# low_side_mcu.net
KiCad netlist of a schematic drawn in EAGLE
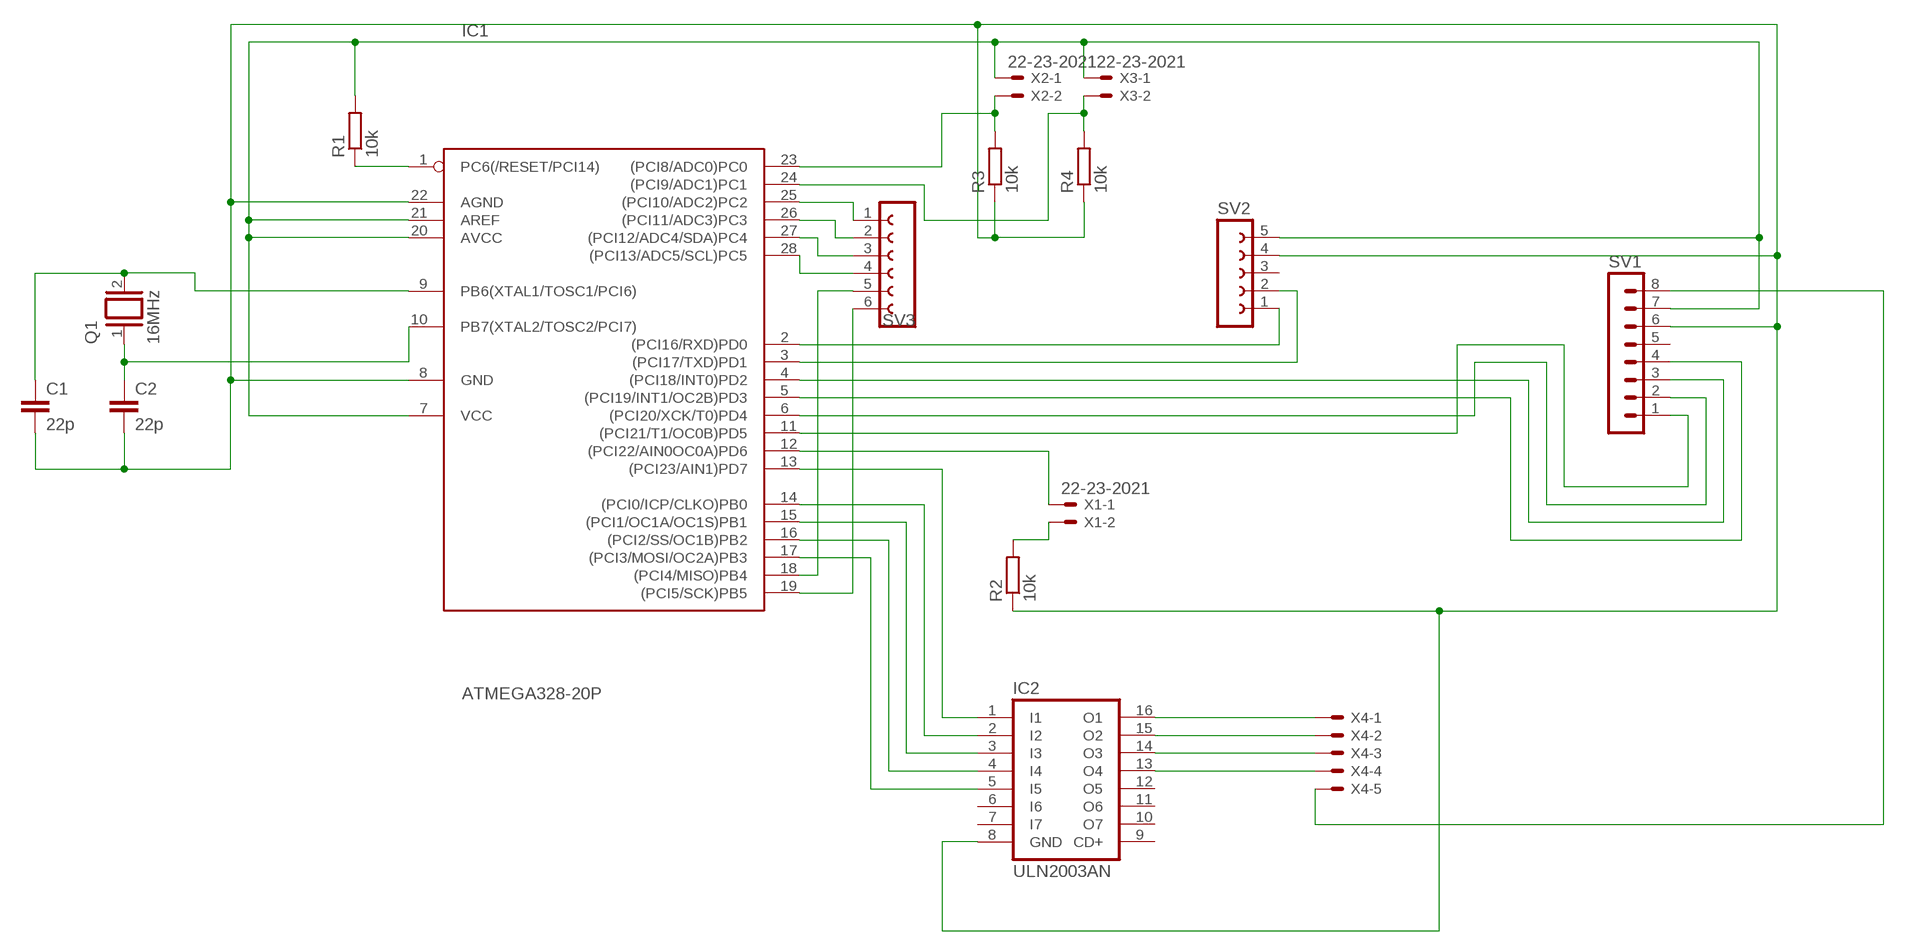
[diagram p0: schematic, sheet 1]

(export (version "E")
  (design (tool "Eeschema 10.0.6"))
  (components
    (comp (ref "C1")
      (value "22p")
      (footprint "eagle-import:C025-024X044")
      (libsource (lib "eagle-import") (part "C-EU025-024X044"))
    )
    (comp (ref "C2")
      (value "22p")
      (footprint "eagle-import:C025-024X044")
      (libsource (lib "eagle-import") (part "C-EU025-024X044"))
    )
    (comp (ref "IC1")
      (value "ATMEGA328-20P")
      (footprint "eagle-import:DIL28-3")
      (libsource (lib "eagle-import") (part "ATMEGA328P-20"))
    )
    (comp (ref "IC2")
      (value "ULN2003AN")
      (footprint "eagle-import:DIL16")
      (libsource (lib "eagle-import") (part "ULN2003AN"))
    )
    (comp (ref "Q1")
      (value "16MHz")
      (footprint "eagle-import:Q")
      (libsource (lib "eagle-import") (part "XTAL"))
    )
    (comp (ref "R1")
      (value "10k")
      (footprint "eagle-import:0204_5")
      (libsource (lib "eagle-import") (part "R-EU_0204/5"))
    )
    (comp (ref "R2")
      (value "10k")
      (footprint "eagle-import:0204_5")
      (libsource (lib "eagle-import") (part "R-EU_0204/5"))
    )
    (comp (ref "R3")
      (value "10k")
      (footprint "eagle-import:0204_5")
      (libsource (lib "eagle-import") (part "R-EU_0204/5"))
    )
    (comp (ref "R4")
      (value "10k")
      (footprint "eagle-import:0204_5")
      (libsource (lib "eagle-import") (part "R-EU_0204/5"))
    )
    (comp (ref "SV1")
      (value "MA08-1")
      (footprint "eagle-import:MA08-1")
      (libsource (lib "eagle-import") (part "MA08-1"))
    )
    (comp (ref "SV2")
      (value "FE05-1")
      (footprint "eagle-import:FE05-1")
      (libsource (lib "eagle-import") (part "FE05-1"))
    )
    (comp (ref "SV3")
      (value "FE06-1")
      (footprint "eagle-import:FE06")
      (libsource (lib "eagle-import") (part "FE06-1"))
    )
    (comp (ref "X1")
      (value "22-23-2021")
      (footprint "eagle-import:22-23-2021")
      (fields (field (name "MF") "MOLEX"))
      (libsource (lib "eagle-import") (part "22-23-2021"))
    )
    (comp (ref "X2")
      (value "22-23-2021")
      (footprint "eagle-import:22-23-2021")
      (fields (field (name "MF") "MOLEX"))
      (libsource (lib "eagle-import") (part "22-23-2021"))
    )
    (comp (ref "X3")
      (value "22-23-2021")
      (footprint "eagle-import:22-23-2021")
      (fields (field (name "MF") "MOLEX"))
      (libsource (lib "eagle-import") (part "22-23-2021"))
    )
    (comp (ref "X4")
      (value "KK-156-5")
      (footprint "eagle-import:KK-156-5")
      (fields (field (name "MF") "MOLEX"))
      (libsource (lib "eagle-import") (part "KK-156-5"))
    )
  )
  (nets
    (net (code "1") (name "Net-(IC1-(PCI0{slash}ICP{slash}CLKO)PB0)") (class "Default")
      (node (ref "IC1") (pin "14") (pinfunction "(PCI0/ICP/CLKO)PB0_14") (pintype "bidirectional"))
      (node (ref "IC2") (pin "2") (pinfunction "I2_2") (pintype "input"))
    )
    (net (code "2") (name "Net-(IC1-(PCI1{slash}OC1A{slash}OC1S)PB1)") (class "Default")
      (node (ref "IC1") (pin "15") (pinfunction "(PCI1/OC1A/OC1S)PB1_15") (pintype "bidirectional"))
      (node (ref "IC2") (pin "3") (pinfunction "I3_3") (pintype "input"))
    )
    (net (code "3") (name "Net-(IC1-(PCI2{slash}SS{slash}OC1B)PB2)") (class "Default")
      (node (ref "IC1") (pin "16") (pinfunction "(PCI2/SS/OC1B)PB2_16") (pintype "bidirectional"))
      (node (ref "IC2") (pin "4") (pinfunction "I4_4") (pintype "input"))
    )
    (net (code "4") (name "Net-(IC1-(PCI3{slash}MOSI{slash}OC2A)PB3)") (class "Default")
      (node (ref "IC1") (pin "17") (pinfunction "(PCI3/MOSI/OC2A)PB3_17") (pintype "bidirectional"))
      (node (ref "IC2") (pin "5") (pinfunction "I5_5") (pintype "input"))
    )
    (net (code "5") (name "Net-(IC1-(PCI4{slash}MISO)PB4)") (class "Default")
      (node (ref "IC1") (pin "18") (pinfunction "(PCI4/MISO)PB4_18") (pintype "bidirectional"))
      (node (ref "SV3") (pin "5") (pinfunction "5_5") (pintype "passive"))
    )
    (net (code "6") (name "Net-(IC1-(PCI5{slash}SCK)PB5)") (class "Default")
      (node (ref "IC1") (pin "19") (pinfunction "(PCI5/SCK)PB5_19") (pintype "bidirectional"))
      (node (ref "SV3") (pin "6") (pinfunction "6_6") (pintype "passive"))
    )
    (net (code "7") (name "Net-(IC1-(PCI8{slash}ADC0)PC0)") (class "Default")
      (node (ref "IC1") (pin "23") (pinfunction "(PCI8/ADC0)PC0_23") (pintype "bidirectional"))
      (node (ref "R3") (pin "2") (pinfunction "2_2") (pintype "passive"))
      (node (ref "X2") (pin "2") (pinfunction "S_2") (pintype "passive"))
    )
    (net (code "8") (name "Net-(IC1-(PCI9{slash}ADC1)PC1)") (class "Default")
      (node (ref "IC1") (pin "24") (pinfunction "(PCI9/ADC1)PC1_24") (pintype "bidirectional"))
      (node (ref "R4") (pin "2") (pinfunction "2_2") (pintype "passive"))
      (node (ref "X3") (pin "2") (pinfunction "S_2") (pintype "passive"))
    )
    (net (code "9") (name "Net-(IC1-(PCI10{slash}ADC2)PC2)") (class "Default")
      (node (ref "IC1") (pin "25") (pinfunction "(PCI10/ADC2)PC2_25") (pintype "bidirectional"))
      (node (ref "SV3") (pin "1") (pinfunction "1_1") (pintype "passive"))
    )
    (net (code "10") (name "Net-(IC1-(PCI11{slash}ADC3)PC3)") (class "Default")
      (node (ref "IC1") (pin "26") (pinfunction "(PCI11/ADC3)PC3_26") (pintype "bidirectional"))
      (node (ref "SV3") (pin "2") (pinfunction "2_2") (pintype "passive"))
    )
    (net (code "11") (name "Net-(IC1-(PCI12{slash}ADC4{slash}SDA)PC4)") (class "Default")
      (node (ref "IC1") (pin "27") (pinfunction "(PCI12/ADC4/SDA)PC4_27") (pintype "bidirectional"))
      (node (ref "SV3") (pin "3") (pinfunction "3_3") (pintype "passive"))
    )
    (net (code "12") (name "Net-(IC1-(PCI13{slash}ADC5{slash}SCL)PC5)") (class "Default")
      (node (ref "IC1") (pin "28") (pinfunction "(PCI13/ADC5/SCL)PC5_28") (pintype "bidirectional"))
      (node (ref "SV3") (pin "4") (pinfunction "4_4") (pintype "passive"))
    )
    (net (code "13") (name "Net-(IC1-(PCI16{slash}RXD)PD0)") (class "Default")
      (node (ref "IC1") (pin "2") (pinfunction "(PCI16/RXD)PD0_2") (pintype "bidirectional"))
      (node (ref "SV2") (pin "1") (pinfunction "1_1") (pintype "passive"))
    )
    (net (code "14") (name "Net-(IC1-(PCI17{slash}TXD)PD1)") (class "Default")
      (node (ref "IC1") (pin "3") (pinfunction "(PCI17/TXD)PD1_3") (pintype "bidirectional"))
      (node (ref "SV2") (pin "2") (pinfunction "2_2") (pintype "passive"))
    )
    (net (code "15") (name "Net-(IC1-(PCI18{slash}INT0)PD2)") (class "Default")
      (node (ref "IC1") (pin "4") (pinfunction "(PCI18/INT0)PD2_4") (pintype "bidirectional"))
      (node (ref "SV1") (pin "3") (pinfunction "3_3") (pintype "passive"))
    )
    (net (code "16") (name "Net-(IC1-(PCI19{slash}INT1{slash}OC2B)PD3)") (class "Default")
      (node (ref "IC1") (pin "5") (pinfunction "(PCI19/INT1/OC2B)PD3_5") (pintype "bidirectional"))
      (node (ref "SV1") (pin "4") (pinfunction "4_4") (pintype "passive"))
    )
    (net (code "17") (name "Net-(IC1-(PCI20{slash}XCK{slash}T0)PD4)") (class "Default")
      (node (ref "IC1") (pin "6") (pinfunction "(PCI20/XCK/T0)PD4_6") (pintype "bidirectional"))
      (node (ref "SV1") (pin "2") (pinfunction "2_2") (pintype "passive"))
    )
    (net (code "18") (name "Net-(IC1-(PCI21{slash}T1{slash}OC0B)PD5)") (class "Default")
      (node (ref "IC1") (pin "11") (pinfunction "(PCI21/T1/OC0B)PD5_11") (pintype "bidirectional"))
      (node (ref "SV1") (pin "1") (pinfunction "1_1") (pintype "passive"))
    )
    (net (code "19") (name "Net-(IC1-(PCI22{slash}AIN0OC0A)PD6)") (class "Default")
      (node (ref "IC1") (pin "12") (pinfunction "(PCI22/AIN0OC0A)PD6_12") (pintype "bidirectional"))
      (node (ref "X1") (pin "1") (pinfunction "S_1") (pintype "passive"))
    )
    (net (code "20") (name "Net-(IC1-(PCI23{slash}AIN1)PD7)") (class "Default")
      (node (ref "IC1") (pin "13") (pinfunction "(PCI23/AIN1)PD7_13") (pintype "bidirectional"))
      (node (ref "IC2") (pin "1") (pinfunction "I1_1") (pintype "input"))
    )
    (net (code "21") (name "Net-(IC1-AGND)") (class "Default")
      (node (ref "C1") (pin "2") (pinfunction "2_2") (pintype "passive"))
      (node (ref "C2") (pin "2") (pinfunction "2_2") (pintype "passive"))
      (node (ref "IC1") (pin "22") (pinfunction "AGND_22") (pintype "bidirectional"))
      (node (ref "IC1") (pin "8") (pinfunction "GND_8") (pintype "bidirectional"))
      (node (ref "IC2") (pin "8") (pinfunction "GND_8") (pintype "power_in"))
      (node (ref "R2") (pin "1") (pinfunction "1_1") (pintype "passive"))
      (node (ref "R3") (pin "1") (pinfunction "1_1") (pintype "passive"))
      (node (ref "R4") (pin "1") (pinfunction "1_1") (pintype "passive"))
      (node (ref "SV1") (pin "6") (pinfunction "6_6") (pintype "passive"))
      (node (ref "SV2") (pin "4") (pinfunction "4_4") (pintype "passive"))
    )
    (net (code "22") (name "Net-(IC1-AREF)") (class "Default")
      (node (ref "IC1") (pin "20") (pinfunction "AVCC_20") (pintype "bidirectional"))
      (node (ref "IC1") (pin "21") (pinfunction "AREF_21") (pintype "bidirectional"))
      (node (ref "IC1") (pin "7") (pinfunction "VCC_7") (pintype "bidirectional"))
      (node (ref "R1") (pin "2") (pinfunction "2_2") (pintype "passive"))
      (node (ref "SV1") (pin "7") (pinfunction "7_7") (pintype "passive"))
      (node (ref "SV2") (pin "5") (pinfunction "5_5") (pintype "passive"))
      (node (ref "X2") (pin "1") (pinfunction "S_1") (pintype "passive"))
      (node (ref "X3") (pin "1") (pinfunction "S_1") (pintype "passive"))
    )
    (net (code "23") (name "Net-(IC1-PB6(XTAL1{slash}TOSC1{slash}PCI6))") (class "Default")
      (node (ref "C1") (pin "1") (pinfunction "1_1") (pintype "passive"))
      (node (ref "IC1") (pin "9") (pinfunction "PB6(XTAL1/TOSC1/PCI6)_9") (pintype "bidirectional"))
      (node (ref "Q1") (pin "2") (pinfunction "2_2") (pintype "passive"))
    )
    (net (code "24") (name "Net-(IC1-PB7(XTAL2{slash}TOSC2{slash}PCI7))") (class "Default")
      (node (ref "C2") (pin "1") (pinfunction "1_1") (pintype "passive"))
      (node (ref "IC1") (pin "10") (pinfunction "PB7(XTAL2/TOSC2/PCI7)_10") (pintype "bidirectional"))
      (node (ref "Q1") (pin "1") (pinfunction "1_1") (pintype "passive"))
    )
    (net (code "25") (name "Net-(IC1-PC6({slash}RESET{slash}PCI14))") (class "Default")
      (node (ref "IC1") (pin "1") (pinfunction "PC6(/RESET/PCI14)_1") (pintype "bidirectional"))
      (node (ref "R1") (pin "1") (pinfunction "1_1") (pintype "passive"))
    )
    (net (code "26") (name "Net-(IC2-O1)") (class "Default")
      (node (ref "IC2") (pin "16") (pinfunction "O1_16") (pintype "open_collector"))
      (node (ref "X4") (pin "1") (pinfunction "S_1") (pintype "passive"))
    )
    (net (code "27") (name "Net-(IC2-O2)") (class "Default")
      (node (ref "IC2") (pin "15") (pinfunction "O2_15") (pintype "open_collector"))
      (node (ref "X4") (pin "2") (pinfunction "S_2") (pintype "passive"))
    )
    (net (code "28") (name "Net-(IC2-O3)") (class "Default")
      (node (ref "IC2") (pin "14") (pinfunction "O3_14") (pintype "open_collector"))
      (node (ref "X4") (pin "3") (pinfunction "S_3") (pintype "passive"))
    )
    (net (code "29") (name "Net-(IC2-O4)") (class "Default")
      (node (ref "IC2") (pin "13") (pinfunction "O4_13") (pintype "open_collector"))
      (node (ref "X4") (pin "4") (pinfunction "S_4") (pintype "passive"))
    )
    (net (code "30") (name "Net-(X1B-S)") (class "Default")
      (node (ref "R2") (pin "2") (pinfunction "2_2") (pintype "passive"))
      (node (ref "X1") (pin "2") (pinfunction "S_2") (pintype "passive"))
    )
    (net (code "31") (name "Net-(X4E-S)") (class "Default")
      (node (ref "SV1") (pin "8") (pinfunction "8_8") (pintype "passive"))
      (node (ref "X4") (pin "5") (pinfunction "S_5") (pintype "passive"))
    )
    (net (code "32") (name "unconnected-(IC2-CD+-Pad9)") (class "Default")
      (node (ref "IC2") (pin "9") (pinfunction "CD+_9") (pintype "passive"))
    )
    (net (code "33") (name "unconnected-(IC2-I6-Pad6)") (class "Default")
      (node (ref "IC2") (pin "6") (pinfunction "I6_6") (pintype "input"))
    )
    (net (code "34") (name "unconnected-(IC2-I7-Pad7)") (class "Default")
      (node (ref "IC2") (pin "7") (pinfunction "I7_7") (pintype "input"))
    )
    (net (code "35") (name "unconnected-(IC2-O5-Pad12)") (class "Default")
      (node (ref "IC2") (pin "12") (pinfunction "O5_12") (pintype "open_collector"))
    )
    (net (code "36") (name "unconnected-(IC2-O6-Pad11)") (class "Default")
      (node (ref "IC2") (pin "11") (pinfunction "O6_11") (pintype "open_collector"))
    )
    (net (code "37") (name "unconnected-(IC2-O7-Pad10)") (class "Default")
      (node (ref "IC2") (pin "10") (pinfunction "O7_10") (pintype "open_collector"))
    )
    (net (code "38") (name "unconnected-(SV1-Pad5)") (class "Default")
      (node (ref "SV1") (pin "5") (pinfunction "5_5") (pintype "passive"))
    )
    (net (code "39") (name "unconnected-(SV2-Pad3)") (class "Default")
      (node (ref "SV2") (pin "3") (pinfunction "3_3") (pintype "passive"))
    )
  )
)
